# ProDoc_P1_2024-12-10.net
KiCad netlist of a schematic drawn in EasyEDA Pro
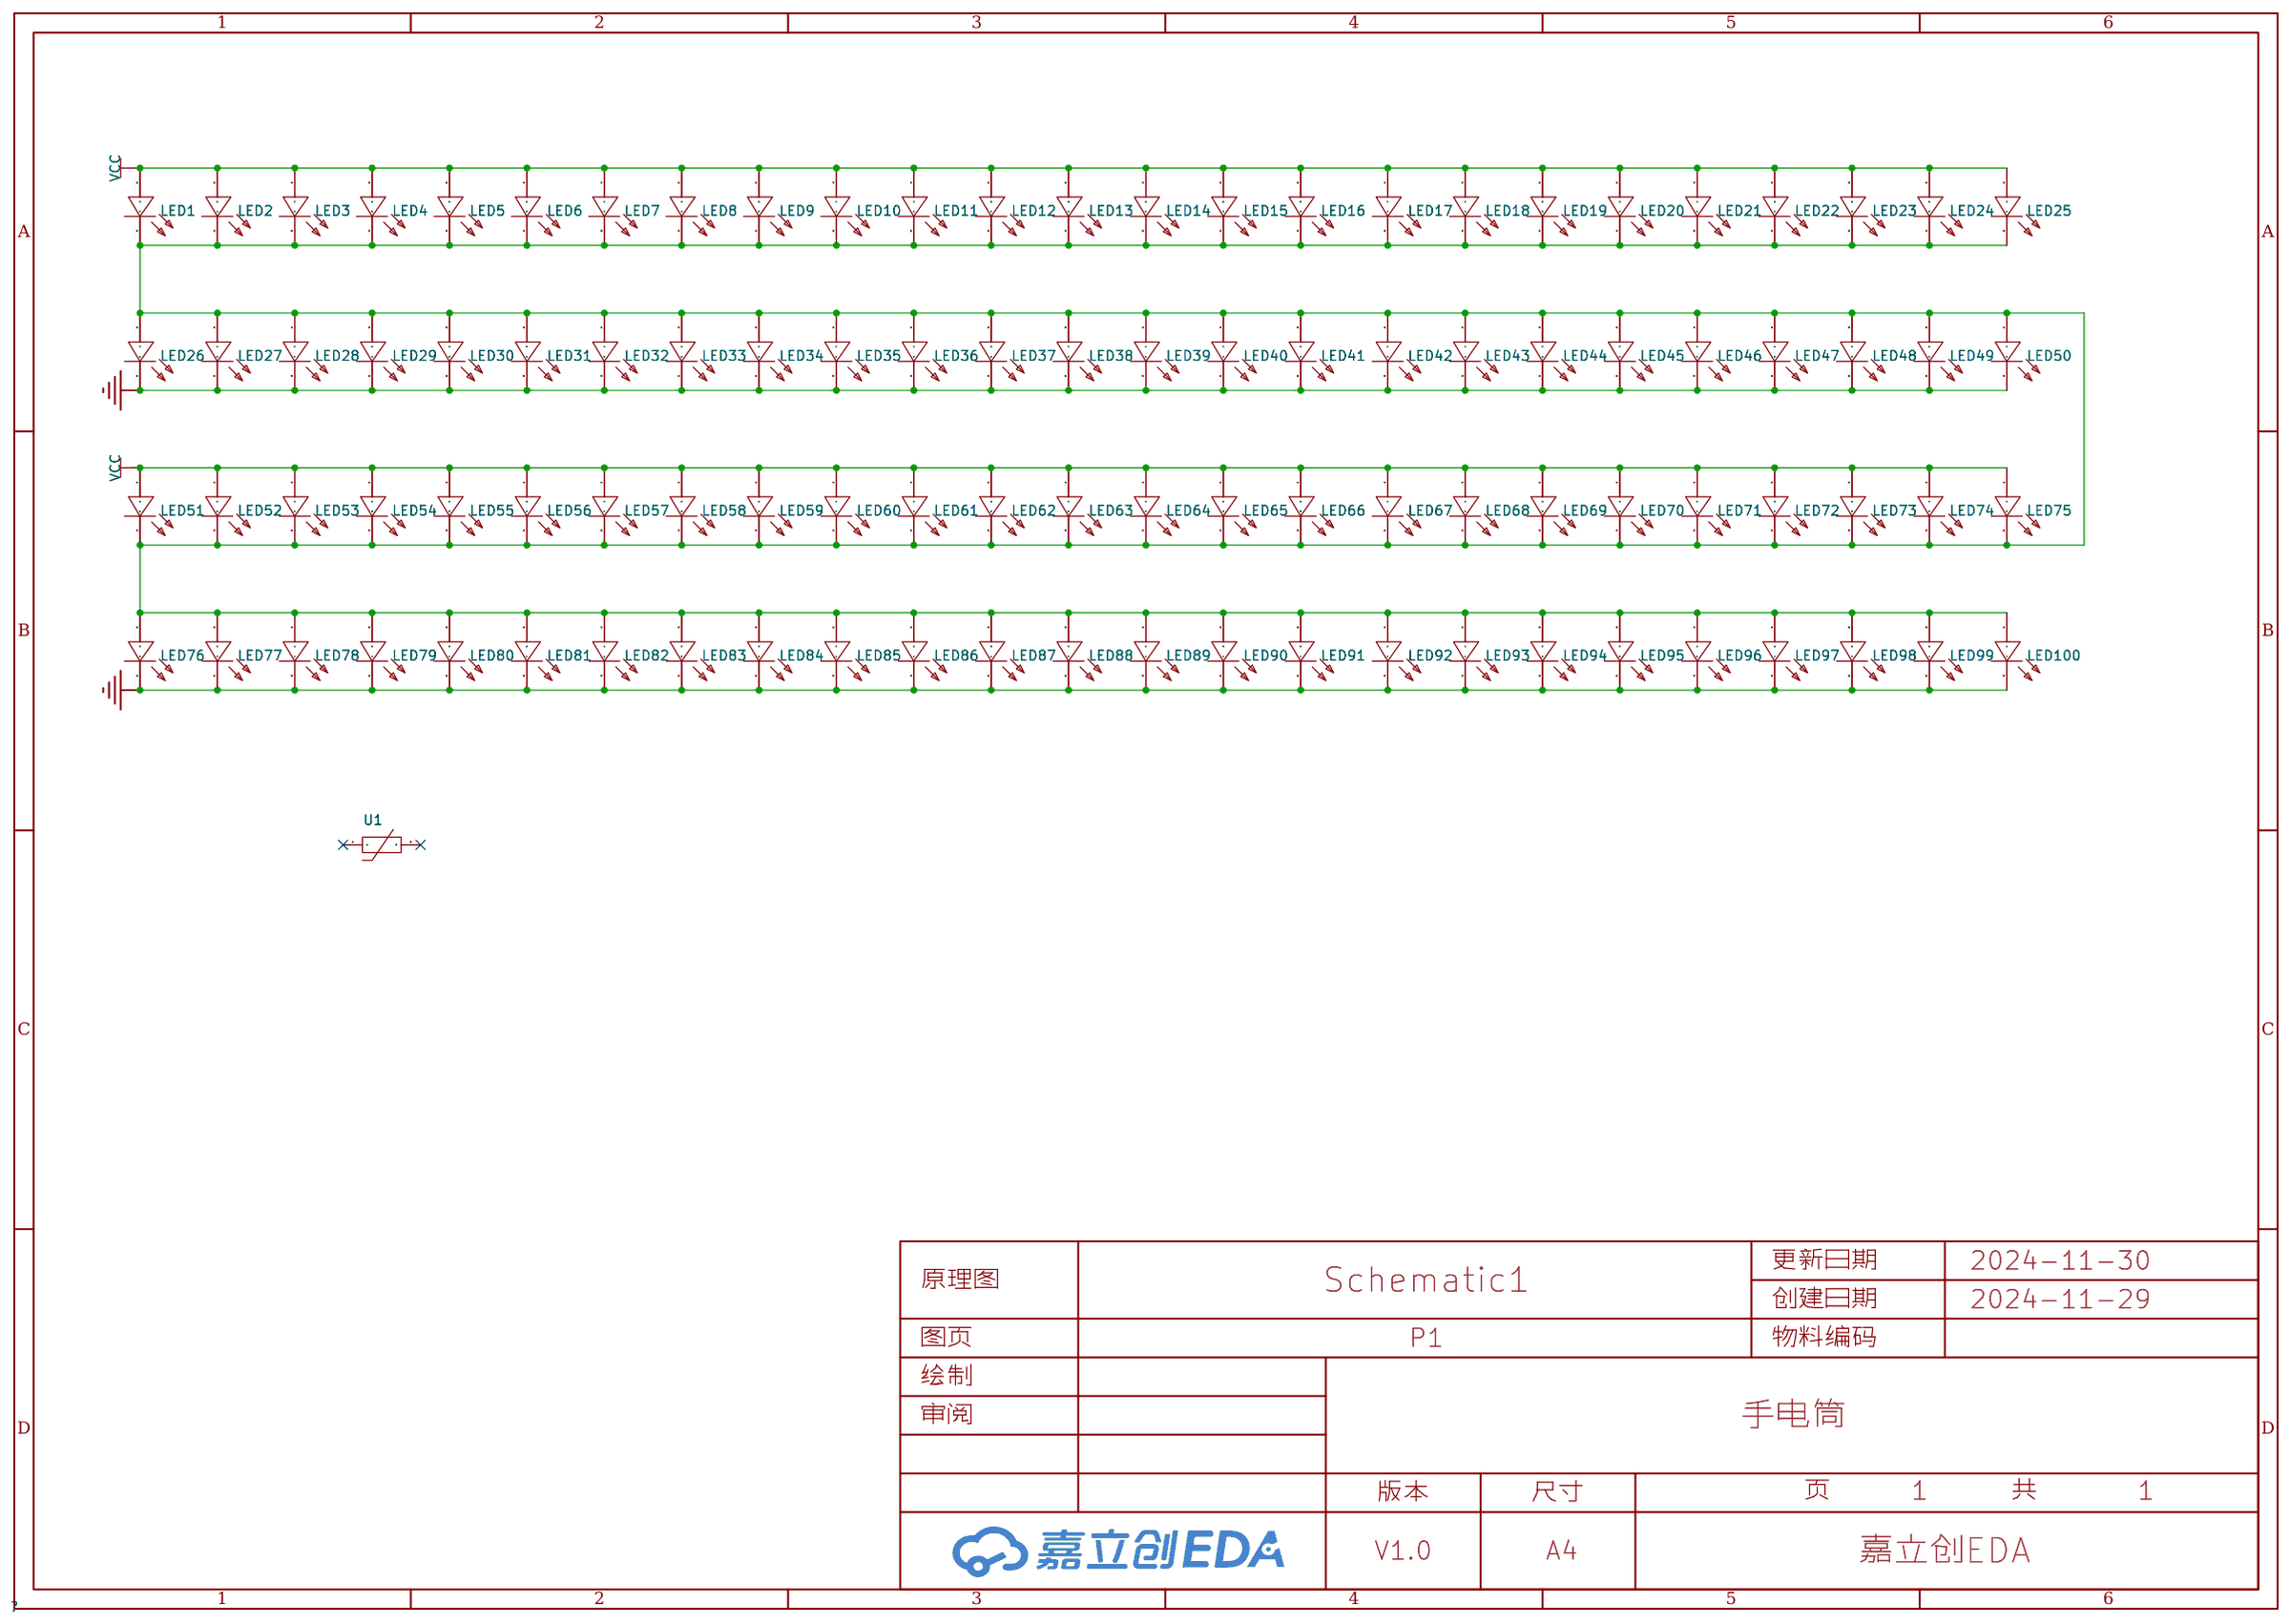
[diagram p0: schematic sheet]

(export (version "E")
  (design (tool "Eeschema 10.0.6"))
  (components
    (comp (ref "LED1")
      (value "SAW9L60A")
      (footprint "easyedapro:LED0805-R-RD")
      (description "色温6000K左右")
      (fields (field (name "Manufacturer") "KENTO"))
      (libsource (lib "easyedapro") (part "whiteLEDSMD"))
    )
    (comp (ref "LED2")
      (value "SAW9L60A")
      (footprint "easyedapro:LED0805-R-RD")
      (description "色温6000K左右")
      (fields (field (name "Manufacturer") "KENTO"))
      (libsource (lib "easyedapro") (part "whiteLEDSMD"))
    )
    (comp (ref "LED3")
      (value "SAW9L60A")
      (footprint "easyedapro:LED0805-R-RD")
      (description "色温6000K左右")
      (fields (field (name "Manufacturer") "KENTO"))
      (libsource (lib "easyedapro") (part "whiteLEDSMD"))
    )
    (comp (ref "LED4")
      (value "SAW9L60A")
      (footprint "easyedapro:LED0805-R-RD")
      (description "色温6000K左右")
      (fields (field (name "Manufacturer") "KENTO"))
      (libsource (lib "easyedapro") (part "whiteLEDSMD"))
    )
    (comp (ref "LED5")
      (value "SAW9L60A")
      (footprint "easyedapro:LED0805-R-RD")
      (description "色温6000K左右")
      (fields (field (name "Manufacturer") "KENTO"))
      (libsource (lib "easyedapro") (part "whiteLEDSMD"))
    )
    (comp (ref "LED6")
      (value "SAW9L60A")
      (footprint "easyedapro:LED0805-R-RD")
      (description "色温6000K左右")
      (fields (field (name "Manufacturer") "KENTO"))
      (libsource (lib "easyedapro") (part "whiteLEDSMD"))
    )
    (comp (ref "LED7")
      (value "SAW9L60A")
      (footprint "easyedapro:LED0805-R-RD")
      (description "色温6000K左右")
      (fields (field (name "Manufacturer") "KENTO"))
      (libsource (lib "easyedapro") (part "whiteLEDSMD"))
    )
    (comp (ref "LED8")
      (value "SAW9L60A")
      (footprint "easyedapro:LED0805-R-RD")
      (description "色温6000K左右")
      (fields (field (name "Manufacturer") "KENTO"))
      (libsource (lib "easyedapro") (part "whiteLEDSMD"))
    )
    (comp (ref "LED9")
      (value "SAW9L60A")
      (footprint "easyedapro:LED0805-R-RD")
      (description "色温6000K左右")
      (fields (field (name "Manufacturer") "KENTO"))
      (libsource (lib "easyedapro") (part "whiteLEDSMD"))
    )
    (comp (ref "LED10")
      (value "SAW9L60A")
      (footprint "easyedapro:LED0805-R-RD")
      (description "色温6000K左右")
      (fields (field (name "Manufacturer") "KENTO"))
      (libsource (lib "easyedapro") (part "whiteLEDSMD"))
    )
    (comp (ref "LED11")
      (value "SAW9L60A")
      (footprint "easyedapro:LED0805-R-RD")
      (description "色温6000K左右")
      (fields (field (name "Manufacturer") "KENTO"))
      (libsource (lib "easyedapro") (part "whiteLEDSMD"))
    )
    (comp (ref "LED12")
      (value "SAW9L60A")
      (footprint "easyedapro:LED0805-R-RD")
      (description "色温6000K左右")
      (fields (field (name "Manufacturer") "KENTO"))
      (libsource (lib "easyedapro") (part "whiteLEDSMD"))
    )
    (comp (ref "LED13")
      (value "SAW9L60A")
      (footprint "easyedapro:LED0805-R-RD")
      (description "色温6000K左右")
      (fields (field (name "Manufacturer") "KENTO"))
      (libsource (lib "easyedapro") (part "whiteLEDSMD"))
    )
    (comp (ref "LED14")
      (value "SAW9L60A")
      (footprint "easyedapro:LED0805-R-RD")
      (description "色温6000K左右")
      (fields (field (name "Manufacturer") "KENTO"))
      (libsource (lib "easyedapro") (part "whiteLEDSMD"))
    )
    (comp (ref "LED15")
      (value "SAW9L60A")
      (footprint "easyedapro:LED0805-R-RD")
      (description "色温6000K左右")
      (fields (field (name "Manufacturer") "KENTO"))
      (libsource (lib "easyedapro") (part "whiteLEDSMD"))
    )
    (comp (ref "LED16")
      (value "SAW9L60A")
      (footprint "easyedapro:LED0805-R-RD")
      (description "色温6000K左右")
      (fields (field (name "Manufacturer") "KENTO"))
      (libsource (lib "easyedapro") (part "whiteLEDSMD"))
    )
    (comp (ref "LED17")
      (value "SAW9L60A")
      (footprint "easyedapro:LED0805-R-RD")
      (description "色温6000K左右")
      (fields (field (name "Manufacturer") "KENTO"))
      (libsource (lib "easyedapro") (part "whiteLEDSMD"))
    )
    (comp (ref "LED18")
      (value "SAW9L60A")
      (footprint "easyedapro:LED0805-R-RD")
      (description "色温6000K左右")
      (fields (field (name "Manufacturer") "KENTO"))
      (libsource (lib "easyedapro") (part "whiteLEDSMD"))
    )
    (comp (ref "LED19")
      (value "SAW9L60A")
      (footprint "easyedapro:LED0805-R-RD")
      (description "色温6000K左右")
      (fields (field (name "Manufacturer") "KENTO"))
      (libsource (lib "easyedapro") (part "whiteLEDSMD"))
    )
    (comp (ref "LED20")
      (value "SAW9L60A")
      (footprint "easyedapro:LED0805-R-RD")
      (description "色温6000K左右")
      (fields (field (name "Manufacturer") "KENTO"))
      (libsource (lib "easyedapro") (part "whiteLEDSMD"))
    )
    (comp (ref "LED21")
      (value "SAW9L60A")
      (footprint "easyedapro:LED0805-R-RD")
      (description "色温6000K左右")
      (fields (field (name "Manufacturer") "KENTO"))
      (libsource (lib "easyedapro") (part "whiteLEDSMD"))
    )
    (comp (ref "LED22")
      (value "SAW9L60A")
      (footprint "easyedapro:LED0805-R-RD")
      (description "色温6000K左右")
      (fields (field (name "Manufacturer") "KENTO"))
      (libsource (lib "easyedapro") (part "whiteLEDSMD"))
    )
    (comp (ref "LED23")
      (value "SAW9L60A")
      (footprint "easyedapro:LED0805-R-RD")
      (description "色温6000K左右")
      (fields (field (name "Manufacturer") "KENTO"))
      (libsource (lib "easyedapro") (part "whiteLEDSMD"))
    )
    (comp (ref "LED24")
      (value "SAW9L60A")
      (footprint "easyedapro:LED0805-R-RD")
      (description "色温6000K左右")
      (fields (field (name "Manufacturer") "KENTO"))
      (libsource (lib "easyedapro") (part "whiteLEDSMD"))
    )
    (comp (ref "LED25")
      (value "SAW9L60A")
      (footprint "easyedapro:LED0805-R-RD")
      (description "色温6000K左右")
      (fields (field (name "Manufacturer") "KENTO"))
      (libsource (lib "easyedapro") (part "whiteLEDSMD"))
    )
    (comp (ref "LED26")
      (value "SAW9L60A")
      (footprint "easyedapro:LED0805-R-RD")
      (description "色温6000K左右")
      (fields (field (name "Manufacturer") "KENTO"))
      (libsource (lib "easyedapro") (part "whiteLEDSMD"))
    )
    (comp (ref "LED27")
      (value "SAW9L60A")
      (footprint "easyedapro:LED0805-R-RD")
      (description "色温6000K左右")
      (fields (field (name "Manufacturer") "KENTO"))
      (libsource (lib "easyedapro") (part "whiteLEDSMD"))
    )
    (comp (ref "LED28")
      (value "SAW9L60A")
      (footprint "easyedapro:LED0805-R-RD")
      (description "色温6000K左右")
      (fields (field (name "Manufacturer") "KENTO"))
      (libsource (lib "easyedapro") (part "whiteLEDSMD"))
    )
    (comp (ref "LED29")
      (value "SAW9L60A")
      (footprint "easyedapro:LED0805-R-RD")
      (description "色温6000K左右")
      (fields (field (name "Manufacturer") "KENTO"))
      (libsource (lib "easyedapro") (part "whiteLEDSMD"))
    )
    (comp (ref "LED30")
      (value "SAW9L60A")
      (footprint "easyedapro:LED0805-R-RD")
      (description "色温6000K左右")
      (fields (field (name "Manufacturer") "KENTO"))
      (libsource (lib "easyedapro") (part "whiteLEDSMD"))
    )
    (comp (ref "LED31")
      (value "SAW9L60A")
      (footprint "easyedapro:LED0805-R-RD")
      (description "色温6000K左右")
      (fields (field (name "Manufacturer") "KENTO"))
      (libsource (lib "easyedapro") (part "whiteLEDSMD"))
    )
    (comp (ref "LED32")
      (value "SAW9L60A")
      (footprint "easyedapro:LED0805-R-RD")
      (description "色温6000K左右")
      (fields (field (name "Manufacturer") "KENTO"))
      (libsource (lib "easyedapro") (part "whiteLEDSMD"))
    )
    (comp (ref "LED33")
      (value "SAW9L60A")
      (footprint "easyedapro:LED0805-R-RD")
      (description "色温6000K左右")
      (fields (field (name "Manufacturer") "KENTO"))
      (libsource (lib "easyedapro") (part "whiteLEDSMD"))
    )
    (comp (ref "LED34")
      (value "SAW9L60A")
      (footprint "easyedapro:LED0805-R-RD")
      (description "色温6000K左右")
      (fields (field (name "Manufacturer") "KENTO"))
      (libsource (lib "easyedapro") (part "whiteLEDSMD"))
    )
    (comp (ref "LED35")
      (value "SAW9L60A")
      (footprint "easyedapro:LED0805-R-RD")
      (description "色温6000K左右")
      (fields (field (name "Manufacturer") "KENTO"))
      (libsource (lib "easyedapro") (part "whiteLEDSMD"))
    )
    (comp (ref "LED36")
      (value "SAW9L60A")
      (footprint "easyedapro:LED0805-R-RD")
      (description "色温6000K左右")
      (fields (field (name "Manufacturer") "KENTO"))
      (libsource (lib "easyedapro") (part "whiteLEDSMD"))
    )
    (comp (ref "LED37")
      (value "SAW9L60A")
      (footprint "easyedapro:LED0805-R-RD")
      (description "色温6000K左右")
      (fields (field (name "Manufacturer") "KENTO"))
      (libsource (lib "easyedapro") (part "whiteLEDSMD"))
    )
    (comp (ref "LED38")
      (value "SAW9L60A")
      (footprint "easyedapro:LED0805-R-RD")
      (description "色温6000K左右")
      (fields (field (name "Manufacturer") "KENTO"))
      (libsource (lib "easyedapro") (part "whiteLEDSMD"))
    )
    (comp (ref "LED39")
      (value "SAW9L60A")
      (footprint "easyedapro:LED0805-R-RD")
      (description "色温6000K左右")
      (fields (field (name "Manufacturer") "KENTO"))
      (libsource (lib "easyedapro") (part "whiteLEDSMD"))
    )
    (comp (ref "LED40")
      (value "SAW9L60A")
      (footprint "easyedapro:LED0805-R-RD")
      (description "色温6000K左右")
      (fields (field (name "Manufacturer") "KENTO"))
      (libsource (lib "easyedapro") (part "whiteLEDSMD"))
    )
    (comp (ref "LED41")
      (value "SAW9L60A")
      (footprint "easyedapro:LED0805-R-RD")
      (description "色温6000K左右")
      (fields (field (name "Manufacturer") "KENTO"))
      (libsource (lib "easyedapro") (part "whiteLEDSMD"))
    )
    (comp (ref "LED42")
      (value "SAW9L60A")
      (footprint "easyedapro:LED0805-R-RD")
      (description "色温6000K左右")
      (fields (field (name "Manufacturer") "KENTO"))
      (libsource (lib "easyedapro") (part "whiteLEDSMD"))
    )
    (comp (ref "LED43")
      (value "SAW9L60A")
      (footprint "easyedapro:LED0805-R-RD")
      (description "色温6000K左右")
      (fields (field (name "Manufacturer") "KENTO"))
      (libsource (lib "easyedapro") (part "whiteLEDSMD"))
    )
    (comp (ref "LED44")
      (value "SAW9L60A")
      (footprint "easyedapro:LED0805-R-RD")
      (description "色温6000K左右")
      (fields (field (name "Manufacturer") "KENTO"))
      (libsource (lib "easyedapro") (part "whiteLEDSMD"))
    )
    (comp (ref "LED45")
      (value "SAW9L60A")
      (footprint "easyedapro:LED0805-R-RD")
      (description "色温6000K左右")
      (fields (field (name "Manufacturer") "KENTO"))
      (libsource (lib "easyedapro") (part "whiteLEDSMD"))
    )
    (comp (ref "LED46")
      (value "SAW9L60A")
      (footprint "easyedapro:LED0805-R-RD")
      (description "色温6000K左右")
      (fields (field (name "Manufacturer") "KENTO"))
      (libsource (lib "easyedapro") (part "whiteLEDSMD"))
    )
    (comp (ref "LED47")
      (value "SAW9L60A")
      (footprint "easyedapro:LED0805-R-RD")
      (description "色温6000K左右")
      (fields (field (name "Manufacturer") "KENTO"))
      (libsource (lib "easyedapro") (part "whiteLEDSMD"))
    )
    (comp (ref "LED48")
      (value "SAW9L60A")
      (footprint "easyedapro:LED0805-R-RD")
      (description "色温6000K左右")
      (fields (field (name "Manufacturer") "KENTO"))
      (libsource (lib "easyedapro") (part "whiteLEDSMD"))
    )
    (comp (ref "LED49")
      (value "SAW9L60A")
      (footprint "easyedapro:LED0805-R-RD")
      (description "色温6000K左右")
      (fields (field (name "Manufacturer") "KENTO"))
      (libsource (lib "easyedapro") (part "whiteLEDSMD"))
    )
    (comp (ref "LED50")
      (value "SAW9L60A")
      (footprint "easyedapro:LED0805-R-RD")
      (description "色温6000K左右")
      (fields (field (name "Manufacturer") "KENTO"))
      (libsource (lib "easyedapro") (part "whiteLEDSMD"))
    )
    (comp (ref "LED51")
      (value "SAW9L60A")
      (footprint "easyedapro:LED0805-R-RD")
      (description "色温6000K左右")
      (fields (field (name "Manufacturer") "KENTO"))
      (libsource (lib "easyedapro") (part "whiteLEDSMD"))
    )
    (comp (ref "LED52")
      (value "SAW9L60A")
      (footprint "easyedapro:LED0805-R-RD")
      (description "色温6000K左右")
      (fields (field (name "Manufacturer") "KENTO"))
      (libsource (lib "easyedapro") (part "whiteLEDSMD"))
    )
    (comp (ref "LED53")
      (value "SAW9L60A")
      (footprint "easyedapro:LED0805-R-RD")
      (description "色温6000K左右")
      (fields (field (name "Manufacturer") "KENTO"))
      (libsource (lib "easyedapro") (part "whiteLEDSMD"))
    )
    (comp (ref "LED54")
      (value "SAW9L60A")
      (footprint "easyedapro:LED0805-R-RD")
      (description "色温6000K左右")
      (fields (field (name "Manufacturer") "KENTO"))
      (libsource (lib "easyedapro") (part "whiteLEDSMD"))
    )
    (comp (ref "LED55")
      (value "SAW9L60A")
      (footprint "easyedapro:LED0805-R-RD")
      (description "色温6000K左右")
      (fields (field (name "Manufacturer") "KENTO"))
      (libsource (lib "easyedapro") (part "whiteLEDSMD"))
    )
    (comp (ref "LED56")
      (value "SAW9L60A")
      (footprint "easyedapro:LED0805-R-RD")
      (description "色温6000K左右")
      (fields (field (name "Manufacturer") "KENTO"))
      (libsource (lib "easyedapro") (part "whiteLEDSMD"))
    )
    (comp (ref "LED57")
      (value "SAW9L60A")
      (footprint "easyedapro:LED0805-R-RD")
      (description "色温6000K左右")
      (fields (field (name "Manufacturer") "KENTO"))
      (libsource (lib "easyedapro") (part "whiteLEDSMD"))
    )
    (comp (ref "LED58")
      (value "SAW9L60A")
      (footprint "easyedapro:LED0805-R-RD")
      (description "色温6000K左右")
      (fields (field (name "Manufacturer") "KENTO"))
      (libsource (lib "easyedapro") (part "whiteLEDSMD"))
    )
    (comp (ref "LED59")
      (value "SAW9L60A")
      (footprint "easyedapro:LED0805-R-RD")
      (description "色温6000K左右")
      (fields (field (name "Manufacturer") "KENTO"))
      (libsource (lib "easyedapro") (part "whiteLEDSMD"))
    )
    (comp (ref "LED60")
      (value "SAW9L60A")
      (footprint "easyedapro:LED0805-R-RD")
      (description "色温6000K左右")
      (fields (field (name "Manufacturer") "KENTO"))
      (libsource (lib "easyedapro") (part "whiteLEDSMD"))
    )
    (comp (ref "LED61")
      (value "SAW9L60A")
      (footprint "easyedapro:LED0805-R-RD")
      (description "色温6000K左右")
      (fields (field (name "Manufacturer") "KENTO"))
      (libsource (lib "easyedapro") (part "whiteLEDSMD"))
    )
    (comp (ref "LED62")
      (value "SAW9L60A")
      (footprint "easyedapro:LED0805-R-RD")
      (description "色温6000K左右")
      (fields (field (name "Manufacturer") "KENTO"))
      (libsource (lib "easyedapro") (part "whiteLEDSMD"))
    )
    (comp (ref "LED63")
      (value "SAW9L60A")
      (footprint "easyedapro:LED0805-R-RD")
      (description "色温6000K左右")
      (fields (field (name "Manufacturer") "KENTO"))
      (libsource (lib "easyedapro") (part "whiteLEDSMD"))
    )
    (comp (ref "LED64")
      (value "SAW9L60A")
      (footprint "easyedapro:LED0805-R-RD")
      (description "色温6000K左右")
      (fields (field (name "Manufacturer") "KENTO"))
      (libsource (lib "easyedapro") (part "whiteLEDSMD"))
    )
    (comp (ref "LED65")
      (value "SAW9L60A")
      (footprint "easyedapro:LED0805-R-RD")
      (description "色温6000K左右")
      (fields (field (name "Manufacturer") "KENTO"))
      (libsource (lib "easyedapro") (part "whiteLEDSMD"))
    )
    (comp (ref "LED66")
      (value "SAW9L60A")
      (footprint "easyedapro:LED0805-R-RD")
      (description "色温6000K左右")
      (fields (field (name "Manufacturer") "KENTO"))
      (libsource (lib "easyedapro") (part "whiteLEDSMD"))
    )
    (comp (ref "LED67")
      (value "SAW9L60A")
      (footprint "easyedapro:LED0805-R-RD")
      (description "色温6000K左右")
      (fields (field (name "Manufacturer") "KENTO"))
      (libsource (lib "easyedapro") (part "whiteLEDSMD"))
    )
    (comp (ref "LED68")
      (value "SAW9L60A")
      (footprint "easyedapro:LED0805-R-RD")
      (description "色温6000K左右")
      (fields (field (name "Manufacturer") "KENTO"))
      (libsource (lib "easyedapro") (part "whiteLEDSMD"))
    )
    (comp (ref "LED69")
      (value "SAW9L60A")
      (footprint "easyedapro:LED0805-R-RD")
      (description "色温6000K左右")
      (fields (field (name "Manufacturer") "KENTO"))
      (libsource (lib "easyedapro") (part "whiteLEDSMD"))
    )
    (comp (ref "LED70")
      (value "SAW9L60A")
      (footprint "easyedapro:LED0805-R-RD")
      (description "色温6000K左右")
      (fields (field (name "Manufacturer") "KENTO"))
      (libsource (lib "easyedapro") (part "whiteLEDSMD"))
    )
    (comp (ref "LED71")
      (value "SAW9L60A")
      (footprint "easyedapro:LED0805-R-RD")
      (description "色温6000K左右")
      (fields (field (name "Manufacturer") "KENTO"))
      (libsource (lib "easyedapro") (part "whiteLEDSMD"))
    )
    (comp (ref "LED72")
      (value "SAW9L60A")
      (footprint "easyedapro:LED0805-R-RD")
      (description "色温6000K左右")
      (fields (field (name "Manufacturer") "KENTO"))
      (libsource (lib "easyedapro") (part "whiteLEDSMD"))
    )
    (comp (ref "LED73")
      (value "SAW9L60A")
      (footprint "easyedapro:LED0805-R-RD")
      (description "色温6000K左右")
      (fields (field (name "Manufacturer") "KENTO"))
      (libsource (lib "easyedapro") (part "whiteLEDSMD"))
    )
    (comp (ref "LED74")
      (value "SAW9L60A")
      (footprint "easyedapro:LED0805-R-RD")
      (description "色温6000K左右")
      (fields (field (name "Manufacturer") "KENTO"))
      (libsource (lib "easyedapro") (part "whiteLEDSMD"))
    )
    (comp (ref "LED75")
      (value "SAW9L60A")
      (footprint "easyedapro:LED0805-R-RD")
      (description "色温6000K左右")
      (fields (field (name "Manufacturer") "KENTO"))
      (libsource (lib "easyedapro") (part "whiteLEDSMD"))
    )
    (comp (ref "LED76")
      (value "SAW9L60A")
      (footprint "easyedapro:LED0805-R-RD")
      (description "色温6000K左右")
      (fields (field (name "Manufacturer") "KENTO"))
      (libsource (lib "easyedapro") (part "whiteLEDSMD"))
    )
    (comp (ref "LED77")
      (value "SAW9L60A")
      (footprint "easyedapro:LED0805-R-RD")
      (description "色温6000K左右")
      (fields (field (name "Manufacturer") "KENTO"))
      (libsource (lib "easyedapro") (part "whiteLEDSMD"))
    )
    (comp (ref "LED78")
      (value "SAW9L60A")
      (footprint "easyedapro:LED0805-R-RD")
      (description "色温6000K左右")
      (fields (field (name "Manufacturer") "KENTO"))
      (libsource (lib "easyedapro") (part "whiteLEDSMD"))
    )
    (comp (ref "LED79")
      (value "SAW9L60A")
      (footprint "easyedapro:LED0805-R-RD")
      (description "色温6000K左右")
      (fields (field (name "Manufacturer") "KENTO"))
      (libsource (lib "easyedapro") (part "whiteLEDSMD"))
    )
    (comp (ref "LED80")
      (value "SAW9L60A")
      (footprint "easyedapro:LED0805-R-RD")
      (description "色温6000K左右")
      (fields (field (name "Manufacturer") "KENTO"))
      (libsource (lib "easyedapro") (part "whiteLEDSMD"))
    )
    (comp (ref "LED81")
      (value "SAW9L60A")
      (footprint "easyedapro:LED0805-R-RD")
      (description "色温6000K左右")
      (fields (field (name "Manufacturer") "KENTO"))
      (libsource (lib "easyedapro") (part "whiteLEDSMD"))
    )
    (comp (ref "LED82")
      (value "SAW9L60A")
      (footprint "easyedapro:LED0805-R-RD")
      (description "色温6000K左右")
      (fields (field (name "Manufacturer") "KENTO"))
      (libsource (lib "easyedapro") (part "whiteLEDSMD"))
    )
    (comp (ref "LED83")
      (value "SAW9L60A")
      (footprint "easyedapro:LED0805-R-RD")
      (description "色温6000K左右")
      (fields (field (name "Manufacturer") "KENTO"))
      (libsource (lib "easyedapro") (part "whiteLEDSMD"))
    )
    (comp (ref "LED84")
      (value "SAW9L60A")
      (footprint "easyedapro:LED0805-R-RD")
      (description "色温6000K左右")
      (fields (field (name "Manufacturer") "KENTO"))
      (libsource (lib "easyedapro") (part "whiteLEDSMD"))
    )
    (comp (ref "LED85")
      (value "SAW9L60A")
      (footprint "easyedapro:LED0805-R-RD")
      (description "色温6000K左右")
      (fields (field (name "Manufacturer") "KENTO"))
      (libsource (lib "easyedapro") (part "whiteLEDSMD"))
    )
    (comp (ref "LED86")
      (value "SAW9L60A")
      (footprint "easyedapro:LED0805-R-RD")
      (description "色温6000K左右")
      (fields (field (name "Manufacturer") "KENTO"))
      (libsource (lib "easyedapro") (part "whiteLEDSMD"))
    )
    (comp (ref "LED87")
      (value "SAW9L60A")
      (footprint "easyedapro:LED0805-R-RD")
      (description "色温6000K左右")
      (fields (field (name "Manufacturer") "KENTO"))
      (libsource (lib "easyedapro") (part "whiteLEDSMD"))
    )
    (comp (ref "LED88")
      (value "SAW9L60A")
      (footprint "easyedapro:LED0805-R-RD")
      (description "色温6000K左右")
      (fields (field (name "Manufacturer") "KENTO"))
      (libsource (lib "easyedapro") (part "whiteLEDSMD"))
    )
    (comp (ref "LED89")
      (value "SAW9L60A")
      (footprint "easyedapro:LED0805-R-RD")
      (description "色温6000K左右")
      (fields (field (name "Manufacturer") "KENTO"))
      (libsource (lib "easyedapro") (part "whiteLEDSMD"))
    )
    (comp (ref "LED90")
      (value "SAW9L60A")
      (footprint "easyedapro:LED0805-R-RD")
      (description "色温6000K左右")
      (fields (field (name "Manufacturer") "KENTO"))
      (libsource (lib "easyedapro") (part "whiteLEDSMD"))
    )
    (comp (ref "LED91")
      (value "SAW9L60A")
      (footprint "easyedapro:LED0805-R-RD")
      (description "色温6000K左右")
      (fields (field (name "Manufacturer") "KENTO"))
      (libsource (lib "easyedapro") (part "whiteLEDSMD"))
    )
    (comp (ref "LED92")
      (value "SAW9L60A")
      (footprint "easyedapro:LED0805-R-RD")
      (description "色温6000K左右")
      (fields (field (name "Manufacturer") "KENTO"))
      (libsource (lib "easyedapro") (part "whiteLEDSMD"))
    )
    (comp (ref "LED93")
      (value "SAW9L60A")
      (footprint "easyedapro:LED0805-R-RD")
      (description "色温6000K左右")
      (fields (field (name "Manufacturer") "KENTO"))
      (libsource (lib "easyedapro") (part "whiteLEDSMD"))
    )
    (comp (ref "LED94")
      (value "SAW9L60A")
      (footprint "easyedapro:LED0805-R-RD")
      (description "色温6000K左右")
      (fields (field (name "Manufacturer") "KENTO"))
      (libsource (lib "easyedapro") (part "whiteLEDSMD"))
    )
    (comp (ref "LED95")
      (value "SAW9L60A")
      (footprint "easyedapro:LED0805-R-RD")
      (description "色温6000K左右")
      (fields (field (name "Manufacturer") "KENTO"))
      (libsource (lib "easyedapro") (part "whiteLEDSMD"))
    )
    (comp (ref "LED96")
      (value "SAW9L60A")
      (footprint "easyedapro:LED0805-R-RD")
      (description "色温6000K左右")
      (fields (field (name "Manufacturer") "KENTO"))
      (libsource (lib "easyedapro") (part "whiteLEDSMD"))
    )
    (comp (ref "LED97")
      (value "SAW9L60A")
      (footprint "easyedapro:LED0805-R-RD")
      (description "色温6000K左右")
      (fields (field (name "Manufacturer") "KENTO"))
      (libsource (lib "easyedapro") (part "whiteLEDSMD"))
    )
    (comp (ref "LED98")
      (value "SAW9L60A")
      (footprint "easyedapro:LED0805-R-RD")
      (description "色温6000K左右")
      (fields (field (name "Manufacturer") "KENTO"))
      (libsource (lib "easyedapro") (part "whiteLEDSMD"))
    )
    (comp (ref "LED99")
      (value "SAW9L60A")
      (footprint "easyedapro:LED0805-R-RD")
      (description "色温6000K左右")
      (fields (field (name "Manufacturer") "KENTO"))
      (libsource (lib "easyedapro") (part "whiteLEDSMD"))
    )
    (comp (ref "LED100")
      (value "SAW9L60A")
      (footprint "easyedapro:LED0805-R-RD")
      (description "色温6000K左右")
      (fields (field (name "Manufacturer") "KENTO"))
      (libsource (lib "easyedapro") (part "whiteLEDSMD"))
    )
    (comp (ref "U1")
      (value "B57355V5104F360")
      (footprint "easyedapro:R0603")
      (description "阻值(25°C):100kΩ;B值(25°C/50°C):4200K;电阻精度:±1%;功率:180mW;B值精度:±1%;")
      (fields (field (name "Manufacturer") "TDK"))
      (libsource (lib "easyedapro") (part "B57355V5104F360"))
    )
  )
  (nets
    (net (code "1") (name "GND") (class "Default")
      (node (ref "LED100") (pin "2") (pinfunction "K_2") (pintype "unspecified"))
      (node (ref "LED26") (pin "2") (pinfunction "K_2") (pintype "unspecified"))
      (node (ref "LED27") (pin "2") (pinfunction "K_2") (pintype "unspecified"))
      (node (ref "LED28") (pin "2") (pinfunction "K_2") (pintype "unspecified"))
      (node (ref "LED29") (pin "2") (pinfunction "K_2") (pintype "unspecified"))
      (node (ref "LED30") (pin "2") (pinfunction "K_2") (pintype "unspecified"))
      (node (ref "LED31") (pin "2") (pinfunction "K_2") (pintype "unspecified"))
      (node (ref "LED32") (pin "2") (pinfunction "K_2") (pintype "unspecified"))
      (node (ref "LED33") (pin "2") (pinfunction "K_2") (pintype "unspecified"))
      (node (ref "LED34") (pin "2") (pinfunction "K_2") (pintype "unspecified"))
      (node (ref "LED35") (pin "2") (pinfunction "K_2") (pintype "unspecified"))
      (node (ref "LED36") (pin "2") (pinfunction "K_2") (pintype "unspecified"))
      (node (ref "LED37") (pin "2") (pinfunction "K_2") (pintype "unspecified"))
      (node (ref "LED38") (pin "2") (pinfunction "K_2") (pintype "unspecified"))
      (node (ref "LED39") (pin "2") (pinfunction "K_2") (pintype "unspecified"))
      (node (ref "LED40") (pin "2") (pinfunction "K_2") (pintype "unspecified"))
      (node (ref "LED41") (pin "2") (pinfunction "K_2") (pintype "unspecified"))
      (node (ref "LED42") (pin "2") (pinfunction "K_2") (pintype "unspecified"))
      (node (ref "LED43") (pin "2") (pinfunction "K_2") (pintype "unspecified"))
      (node (ref "LED44") (pin "2") (pinfunction "K_2") (pintype "unspecified"))
      (node (ref "LED45") (pin "2") (pinfunction "K_2") (pintype "unspecified"))
      (node (ref "LED46") (pin "2") (pinfunction "K_2") (pintype "unspecified"))
      (node (ref "LED47") (pin "2") (pinfunction "K_2") (pintype "unspecified"))
      (node (ref "LED48") (pin "2") (pinfunction "K_2") (pintype "unspecified"))
      (node (ref "LED49") (pin "2") (pinfunction "K_2") (pintype "unspecified"))
      (node (ref "LED50") (pin "2") (pinfunction "K_2") (pintype "unspecified"))
      (node (ref "LED76") (pin "2") (pinfunction "K_2") (pintype "unspecified"))
      (node (ref "LED77") (pin "2") (pinfunction "K_2") (pintype "unspecified"))
      (node (ref "LED78") (pin "2") (pinfunction "K_2") (pintype "unspecified"))
      (node (ref "LED79") (pin "2") (pinfunction "K_2") (pintype "unspecified"))
      (node (ref "LED80") (pin "2") (pinfunction "K_2") (pintype "unspecified"))
      (node (ref "LED81") (pin "2") (pinfunction "K_2") (pintype "unspecified"))
      (node (ref "LED82") (pin "2") (pinfunction "K_2") (pintype "unspecified"))
      (node (ref "LED83") (pin "2") (pinfunction "K_2") (pintype "unspecified"))
      (node (ref "LED84") (pin "2") (pinfunction "K_2") (pintype "unspecified"))
      (node (ref "LED85") (pin "2") (pinfunction "K_2") (pintype "unspecified"))
      (node (ref "LED86") (pin "2") (pinfunction "K_2") (pintype "unspecified"))
      (node (ref "LED87") (pin "2") (pinfunction "K_2") (pintype "unspecified"))
      (node (ref "LED88") (pin "2") (pinfunction "K_2") (pintype "unspecified"))
      (node (ref "LED89") (pin "2") (pinfunction "K_2") (pintype "unspecified"))
      (node (ref "LED90") (pin "2") (pinfunction "K_2") (pintype "unspecified"))
      (node (ref "LED91") (pin "2") (pinfunction "K_2") (pintype "unspecified"))
      (node (ref "LED92") (pin "2") (pinfunction "K_2") (pintype "unspecified"))
      (node (ref "LED93") (pin "2") (pinfunction "K_2") (pintype "unspecified"))
      (node (ref "LED94") (pin "2") (pinfunction "K_2") (pintype "unspecified"))
      (node (ref "LED95") (pin "2") (pinfunction "K_2") (pintype "unspecified"))
      (node (ref "LED96") (pin "2") (pinfunction "K_2") (pintype "unspecified"))
      (node (ref "LED97") (pin "2") (pinfunction "K_2") (pintype "unspecified"))
      (node (ref "LED98") (pin "2") (pinfunction "K_2") (pintype "unspecified"))
      (node (ref "LED99") (pin "2") (pinfunction "K_2") (pintype "unspecified"))
    )
    (net (code "2") (name "Net-(LED1-K)") (class "Default")
      (node (ref "LED1") (pin "2") (pinfunction "K_2") (pintype "unspecified"))
      (node (ref "LED10") (pin "2") (pinfunction "K_2") (pintype "unspecified"))
      (node (ref "LED100") (pin "1") (pinfunction "A_1") (pintype "unspecified"))
      (node (ref "LED11") (pin "2") (pinfunction "K_2") (pintype "unspecified"))
      (node (ref "LED12") (pin "2") (pinfunction "K_2") (pintype "unspecified"))
      (node (ref "LED13") (pin "2") (pinfunction "K_2") (pintype "unspecified"))
      (node (ref "LED14") (pin "2") (pinfunction "K_2") (pintype "unspecified"))
      (node (ref "LED15") (pin "2") (pinfunction "K_2") (pintype "unspecified"))
      (node (ref "LED16") (pin "2") (pinfunction "K_2") (pintype "unspecified"))
      (node (ref "LED17") (pin "2") (pinfunction "K_2") (pintype "unspecified"))
      (node (ref "LED18") (pin "2") (pinfunction "K_2") (pintype "unspecified"))
      (node (ref "LED19") (pin "2") (pinfunction "K_2") (pintype "unspecified"))
      (node (ref "LED2") (pin "2") (pinfunction "K_2") (pintype "unspecified"))
      (node (ref "LED20") (pin "2") (pinfunction "K_2") (pintype "unspecified"))
      (node (ref "LED21") (pin "2") (pinfunction "K_2") (pintype "unspecified"))
      (node (ref "LED22") (pin "2") (pinfunction "K_2") (pintype "unspecified"))
      (node (ref "LED23") (pin "2") (pinfunction "K_2") (pintype "unspecified"))
      (node (ref "LED24") (pin "2") (pinfunction "K_2") (pintype "unspecified"))
      (node (ref "LED25") (pin "2") (pinfunction "K_2") (pintype "unspecified"))
      (node (ref "LED26") (pin "1") (pinfunction "A_1") (pintype "unspecified"))
      (node (ref "LED27") (pin "1") (pinfunction "A_1") (pintype "unspecified"))
      (node (ref "LED28") (pin "1") (pinfunction "A_1") (pintype "unspecified"))
      (node (ref "LED29") (pin "1") (pinfunction "A_1") (pintype "unspecified"))
      (node (ref "LED3") (pin "2") (pinfunction "K_2") (pintype "unspecified"))
      (node (ref "LED30") (pin "1") (pinfunction "A_1") (pintype "unspecified"))
      (node (ref "LED31") (pin "1") (pinfunction "A_1") (pintype "unspecified"))
      (node (ref "LED32") (pin "1") (pinfunction "A_1") (pintype "unspecified"))
      (node (ref "LED33") (pin "1") (pinfunction "A_1") (pintype "unspecified"))
      (node (ref "LED34") (pin "1") (pinfunction "A_1") (pintype "unspecified"))
      (node (ref "LED35") (pin "1") (pinfunction "A_1") (pintype "unspecified"))
      (node (ref "LED36") (pin "1") (pinfunction "A_1") (pintype "unspecified"))
      (node (ref "LED37") (pin "1") (pinfunction "A_1") (pintype "unspecified"))
      (node (ref "LED38") (pin "1") (pinfunction "A_1") (pintype "unspecified"))
      (node (ref "LED39") (pin "1") (pinfunction "A_1") (pintype "unspecified"))
      (node (ref "LED4") (pin "2") (pinfunction "K_2") (pintype "unspecified"))
      (node (ref "LED40") (pin "1") (pinfunction "A_1") (pintype "unspecified"))
      (node (ref "LED41") (pin "1") (pinfunction "A_1") (pintype "unspecified"))
      (node (ref "LED42") (pin "1") (pinfunction "A_1") (pintype "unspecified"))
      (node (ref "LED43") (pin "1") (pinfunction "A_1") (pintype "unspecified"))
      (node (ref "LED44") (pin "1") (pinfunction "A_1") (pintype "unspecified"))
      (node (ref "LED45") (pin "1") (pinfunction "A_1") (pintype "unspecified"))
      (node (ref "LED46") (pin "1") (pinfunction "A_1") (pintype "unspecified"))
      (node (ref "LED47") (pin "1") (pinfunction "A_1") (pintype "unspecified"))
      (node (ref "LED48") (pin "1") (pinfunction "A_1") (pintype "unspecified"))
      (node (ref "LED49") (pin "1") (pinfunction "A_1") (pintype "unspecified"))
      (node (ref "LED5") (pin "2") (pinfunction "K_2") (pintype "unspecified"))
      (node (ref "LED50") (pin "1") (pinfunction "A_1") (pintype "unspecified"))
      (node (ref "LED51") (pin "2") (pinfunction "K_2") (pintype "unspecified"))
      (node (ref "LED52") (pin "2") (pinfunction "K_2") (pintype "unspecified"))
      (node (ref "LED53") (pin "2") (pinfunction "K_2") (pintype "unspecified"))
      (node (ref "LED54") (pin "2") (pinfunction "K_2") (pintype "unspecified"))
      (node (ref "LED55") (pin "2") (pinfunction "K_2") (pintype "unspecified"))
      (node (ref "LED56") (pin "2") (pinfunction "K_2") (pintype "unspecified"))
      (node (ref "LED57") (pin "2") (pinfunction "K_2") (pintype "unspecified"))
      (node (ref "LED58") (pin "2") (pinfunction "K_2") (pintype "unspecified"))
      (node (ref "LED59") (pin "2") (pinfunction "K_2") (pintype "unspecified"))
      (node (ref "LED6") (pin "2") (pinfunction "K_2") (pintype "unspecified"))
      (node (ref "LED60") (pin "2") (pinfunction "K_2") (pintype "unspecified"))
      (node (ref "LED61") (pin "2") (pinfunction "K_2") (pintype "unspecified"))
      (node (ref "LED62") (pin "2") (pinfunction "K_2") (pintype "unspecified"))
      (node (ref "LED63") (pin "2") (pinfunction "K_2") (pintype "unspecified"))
      (node (ref "LED64") (pin "2") (pinfunction "K_2") (pintype "unspecified"))
      (node (ref "LED65") (pin "2") (pinfunction "K_2") (pintype "unspecified"))
      (node (ref "LED66") (pin "2") (pinfunction "K_2") (pintype "unspecified"))
      (node (ref "LED67") (pin "2") (pinfunction "K_2") (pintype "unspecified"))
      (node (ref "LED68") (pin "2") (pinfunction "K_2") (pintype "unspecified"))
      (node (ref "LED69") (pin "2") (pinfunction "K_2") (pintype "unspecified"))
      (node (ref "LED7") (pin "2") (pinfunction "K_2") (pintype "unspecified"))
      (node (ref "LED70") (pin "2") (pinfunction "K_2") (pintype "unspecified"))
      (node (ref "LED71") (pin "2") (pinfunction "K_2") (pintype "unspecified"))
      (node (ref "LED72") (pin "2") (pinfunction "K_2") (pintype "unspecified"))
      (node (ref "LED73") (pin "2") (pinfunction "K_2") (pintype "unspecified"))
      (node (ref "LED74") (pin "2") (pinfunction "K_2") (pintype "unspecified"))
      (node (ref "LED75") (pin "2") (pinfunction "K_2") (pintype "unspecified"))
      (node (ref "LED76") (pin "1") (pinfunction "A_1") (pintype "unspecified"))
      (node (ref "LED77") (pin "1") (pinfunction "A_1") (pintype "unspecified"))
      (node (ref "LED78") (pin "1") (pinfunction "A_1") (pintype "unspecified"))
      (node (ref "LED79") (pin "1") (pinfunction "A_1") (pintype "unspecified"))
      (node (ref "LED8") (pin "2") (pinfunction "K_2") (pintype "unspecified"))
      (node (ref "LED80") (pin "1") (pinfunction "A_1") (pintype "unspecified"))
      (node (ref "LED81") (pin "1") (pinfunction "A_1") (pintype "unspecified"))
      (node (ref "LED82") (pin "1") (pinfunction "A_1") (pintype "unspecified"))
      (node (ref "LED83") (pin "1") (pinfunction "A_1") (pintype "unspecified"))
      (node (ref "LED84") (pin "1") (pinfunction "A_1") (pintype "unspecified"))
      (node (ref "LED85") (pin "1") (pinfunction "A_1") (pintype "unspecified"))
      (node (ref "LED86") (pin "1") (pinfunction "A_1") (pintype "unspecified"))
      (node (ref "LED87") (pin "1") (pinfunction "A_1") (pintype "unspecified"))
      (node (ref "LED88") (pin "1") (pinfunction "A_1") (pintype "unspecified"))
      (node (ref "LED89") (pin "1") (pinfunction "A_1") (pintype "unspecified"))
      (node (ref "LED9") (pin "2") (pinfunction "K_2") (pintype "unspecified"))
      (node (ref "LED90") (pin "1") (pinfunction "A_1") (pintype "unspecified"))
      (node (ref "LED91") (pin "1") (pinfunction "A_1") (pintype "unspecified"))
      (node (ref "LED92") (pin "1") (pinfunction "A_1") (pintype "unspecified"))
      (node (ref "LED93") (pin "1") (pinfunction "A_1") (pintype "unspecified"))
      (node (ref "LED94") (pin "1") (pinfunction "A_1") (pintype "unspecified"))
      (node (ref "LED95") (pin "1") (pinfunction "A_1") (pintype "unspecified"))
      (node (ref "LED96") (pin "1") (pinfunction "A_1") (pintype "unspecified"))
      (node (ref "LED97") (pin "1") (pinfunction "A_1") (pintype "unspecified"))
      (node (ref "LED98") (pin "1") (pinfunction "A_1") (pintype "unspecified"))
      (node (ref "LED99") (pin "1") (pinfunction "A_1") (pintype "unspecified"))
    )
    (net (code "3") (name "VCC") (class "Default")
      (node (ref "LED1") (pin "1") (pinfunction "A_1") (pintype "unspecified"))
      (node (ref "LED10") (pin "1") (pinfunction "A_1") (pintype "unspecified"))
      (node (ref "LED11") (pin "1") (pinfunction "A_1") (pintype "unspecified"))
      (node (ref "LED12") (pin "1") (pinfunction "A_1") (pintype "unspecified"))
      (node (ref "LED13") (pin "1") (pinfunction "A_1") (pintype "unspecified"))
      (node (ref "LED14") (pin "1") (pinfunction "A_1") (pintype "unspecified"))
      (node (ref "LED15") (pin "1") (pinfunction "A_1") (pintype "unspecified"))
      (node (ref "LED16") (pin "1") (pinfunction "A_1") (pintype "unspecified"))
      (node (ref "LED17") (pin "1") (pinfunction "A_1") (pintype "unspecified"))
      (node (ref "LED18") (pin "1") (pinfunction "A_1") (pintype "unspecified"))
      (node (ref "LED19") (pin "1") (pinfunction "A_1") (pintype "unspecified"))
      (node (ref "LED2") (pin "1") (pinfunction "A_1") (pintype "unspecified"))
      (node (ref "LED20") (pin "1") (pinfunction "A_1") (pintype "unspecified"))
      (node (ref "LED21") (pin "1") (pinfunction "A_1") (pintype "unspecified"))
      (node (ref "LED22") (pin "1") (pinfunction "A_1") (pintype "unspecified"))
      (node (ref "LED23") (pin "1") (pinfunction "A_1") (pintype "unspecified"))
      (node (ref "LED24") (pin "1") (pinfunction "A_1") (pintype "unspecified"))
      (node (ref "LED25") (pin "1") (pinfunction "A_1") (pintype "unspecified"))
      (node (ref "LED3") (pin "1") (pinfunction "A_1") (pintype "unspecified"))
      (node (ref "LED4") (pin "1") (pinfunction "A_1") (pintype "unspecified"))
      (node (ref "LED5") (pin "1") (pinfunction "A_1") (pintype "unspecified"))
      (node (ref "LED51") (pin "1") (pinfunction "A_1") (pintype "unspecified"))
      (node (ref "LED52") (pin "1") (pinfunction "A_1") (pintype "unspecified"))
      (node (ref "LED53") (pin "1") (pinfunction "A_1") (pintype "unspecified"))
      (node (ref "LED54") (pin "1") (pinfunction "A_1") (pintype "unspecified"))
      (node (ref "LED55") (pin "1") (pinfunction "A_1") (pintype "unspecified"))
      (node (ref "LED56") (pin "1") (pinfunction "A_1") (pintype "unspecified"))
      (node (ref "LED57") (pin "1") (pinfunction "A_1") (pintype "unspecified"))
      (node (ref "LED58") (pin "1") (pinfunction "A_1") (pintype "unspecified"))
      (node (ref "LED59") (pin "1") (pinfunction "A_1") (pintype "unspecified"))
      (node (ref "LED6") (pin "1") (pinfunction "A_1") (pintype "unspecified"))
      (node (ref "LED60") (pin "1") (pinfunction "A_1") (pintype "unspecified"))
      (node (ref "LED61") (pin "1") (pinfunction "A_1") (pintype "unspecified"))
      (node (ref "LED62") (pin "1") (pinfunction "A_1") (pintype "unspecified"))
      (node (ref "LED63") (pin "1") (pinfunction "A_1") (pintype "unspecified"))
      (node (ref "LED64") (pin "1") (pinfunction "A_1") (pintype "unspecified"))
      (node (ref "LED65") (pin "1") (pinfunction "A_1") (pintype "unspecified"))
      (node (ref "LED66") (pin "1") (pinfunction "A_1") (pintype "unspecified"))
      (node (ref "LED67") (pin "1") (pinfunction "A_1") (pintype "unspecified"))
      (node (ref "LED68") (pin "1") (pinfunction "A_1") (pintype "unspecified"))
      (node (ref "LED69") (pin "1") (pinfunction "A_1") (pintype "unspecified"))
      (node (ref "LED7") (pin "1") (pinfunction "A_1") (pintype "unspecified"))
      (node (ref "LED70") (pin "1") (pinfunction "A_1") (pintype "unspecified"))
      (node (ref "LED71") (pin "1") (pinfunction "A_1") (pintype "unspecified"))
      (node (ref "LED72") (pin "1") (pinfunction "A_1") (pintype "unspecified"))
      (node (ref "LED73") (pin "1") (pinfunction "A_1") (pintype "unspecified"))
      (node (ref "LED74") (pin "1") (pinfunction "A_1") (pintype "unspecified"))
      (node (ref "LED75") (pin "1") (pinfunction "A_1") (pintype "unspecified"))
      (node (ref "LED8") (pin "1") (pinfunction "A_1") (pintype "unspecified"))
      (node (ref "LED9") (pin "1") (pinfunction "A_1") (pintype "unspecified"))
    )
    (net (code "4") (name "unconnected-(U1-Pad1)") (class "Default")
      (node (ref "U1") (pin "1") (pinfunction "1_1") (pintype "unspecified+no_connect"))
    )
    (net (code "5") (name "unconnected-(U1-Pad2)") (class "Default")
      (node (ref "U1") (pin "2") (pinfunction "2_2") (pintype "unspecified+no_connect"))
    )
  )
)
